# stepper.net
KiCad netlist of a schematic drawn in EAGLE
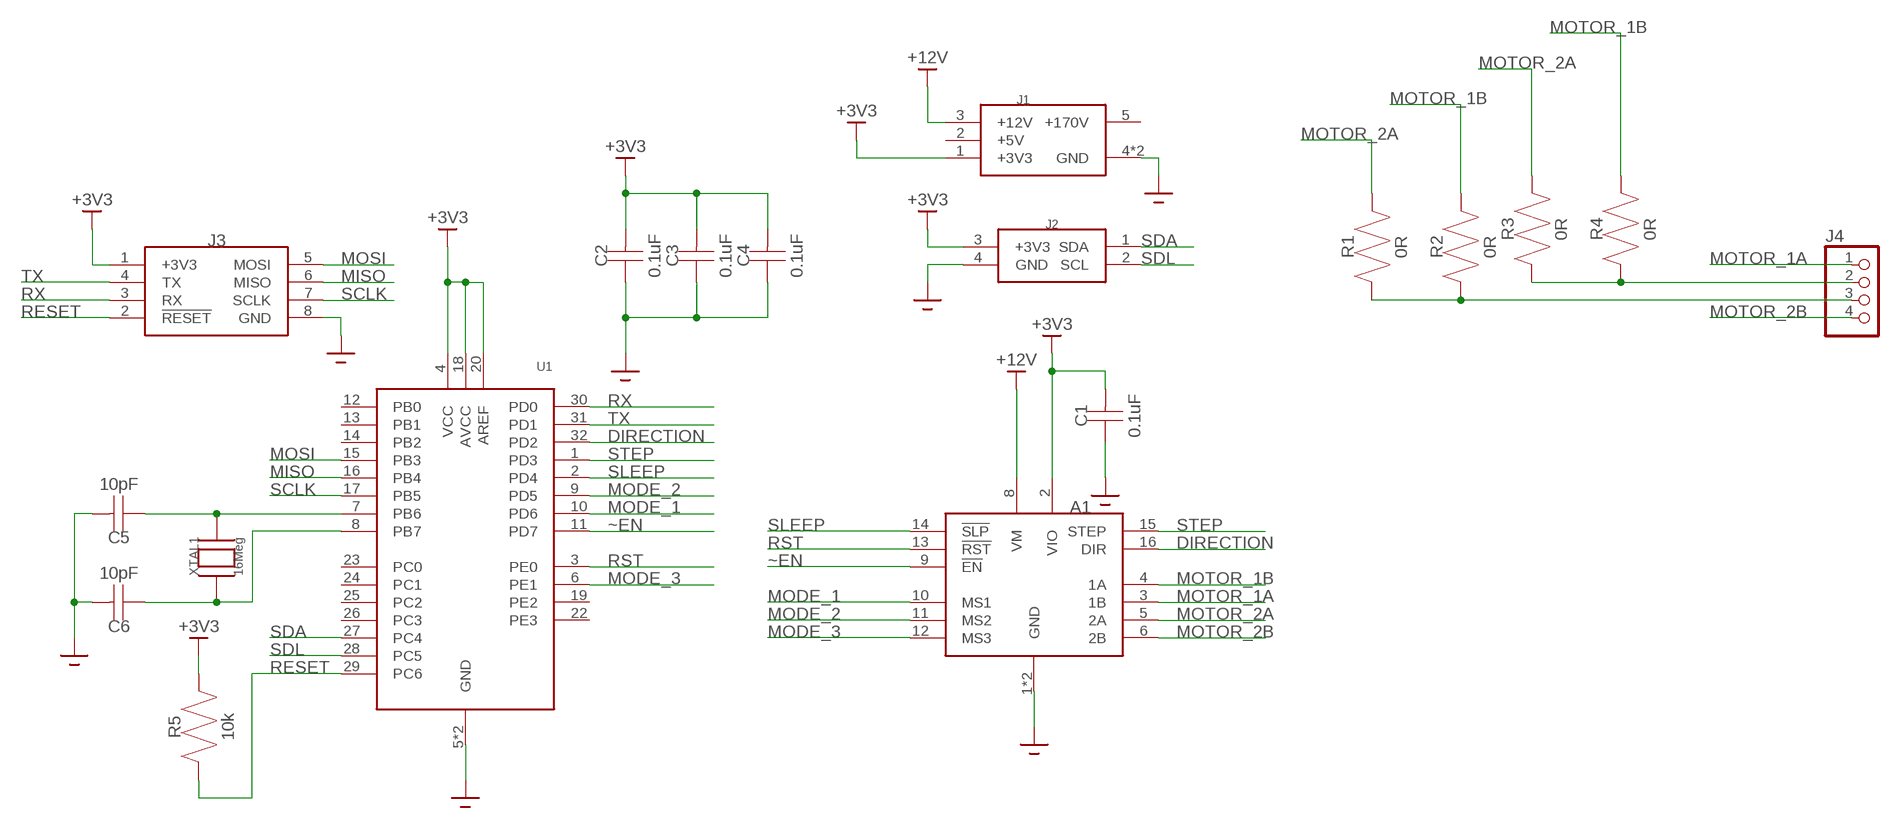
[diagram p0: schematic, sheet 1]

(export (version "E")
  (design (tool "Eeschema 10.0.6"))
  (components
    (comp (ref "A1")
      (value "STEPPER_DRIVER")
      (footprint "eagle-import:STEPPER_DRIVER")
      (libsource (lib "eagle-import") (part "STEPPER_DRIVER"))
    )
    (comp (ref "C1")
      (value "0.1uF")
      (footprint "eagle-import:0402")
      (libsource (lib "eagle-import") (part "CAPACITOR0402"))
    )
    (comp (ref "C2")
      (value "0.1uF")
      (footprint "eagle-import:0402")
      (libsource (lib "eagle-import") (part "CAPACITOR0402"))
    )
    (comp (ref "C3")
      (value "0.1uF")
      (footprint "eagle-import:0402")
      (libsource (lib "eagle-import") (part "CAPACITOR0402"))
    )
    (comp (ref "C4")
      (value "0.1uF")
      (footprint "eagle-import:0402")
      (libsource (lib "eagle-import") (part "CAPACITOR0402"))
    )
    (comp (ref "C5")
      (value "10pF")
      (footprint "eagle-import:0402")
      (libsource (lib "eagle-import") (part "CAPACITOR0402"))
    )
    (comp (ref "C6")
      (value "10pF")
      (footprint "eagle-import:0402")
      (libsource (lib "eagle-import") (part "CAPACITOR0402"))
    )
    (comp (ref "J1")
      (value "1-770969-0")
      (footprint "eagle-import:1-770969-0")
      (libsource (lib "eagle-import") (part "1-770969-0"))
    )
    (comp (ref "J2")
      (value "1-770968-0")
      (footprint "eagle-import:1-770968-0")
      (libsource (lib "eagle-import") (part "1-770968-0"))
    )
    (comp (ref "J3")
      (value "DF1BZ-8DP-2.5DSA")
      (footprint "eagle-import:DF1BZ-8DP-2.5DSA")
      (libsource (lib "eagle-import") (part "DF1BZ-8DP-2.5DSA"))
    )
    (comp (ref "J4")
      (value "S4B-XH-A")
      (footprint "eagle-import:S4B-XH-A")
      (libsource (lib "eagle-import") (part "S4B-XH-A"))
    )
    (comp (ref "R1")
      (value "0R")
      (footprint "eagle-import:0402")
      (libsource (lib "eagle-import") (part "RESISTOR0402"))
    )
    (comp (ref "R2")
      (value "0R")
      (footprint "eagle-import:0402")
      (libsource (lib "eagle-import") (part "RESISTOR0402"))
    )
    (comp (ref "R3")
      (value "0R")
      (footprint "eagle-import:0402")
      (libsource (lib "eagle-import") (part "RESISTOR0402"))
    )
    (comp (ref "R4")
      (value "0R")
      (footprint "eagle-import:0402")
      (libsource (lib "eagle-import") (part "RESISTOR0402"))
    )
    (comp (ref "R5")
      (value "10k")
      (footprint "eagle-import:0402")
      (libsource (lib "eagle-import") (part "RESISTOR0402"))
    )
    (comp (ref "U1")
      (value "ATMEGA328PB32-TQFP")
      (footprint "eagle-import:ATMEGA328PB")
      (libsource (lib "eagle-import") (part "ATMEGA328PB32-TQFP"))
    )
    (comp (ref "XTAL1")
      (value "16Meg")
      (footprint "eagle-import:XRCGB")
      (libsource (lib "eagle-import") (part "XRCGB"))
    )
  )
  (nets
    (net (code "1") (name "+3V3") (class "Default")
      (node (ref "A1") (pin "2") (pinfunction "VIO_2") (pintype "power_in"))
      (node (ref "C1") (pin "2") (pinfunction "P$2_2") (pintype "passive"))
      (node (ref "C2") (pin "2") (pinfunction "P$2_2") (pintype "passive"))
      (node (ref "C3") (pin "2") (pinfunction "P$2_2") (pintype "passive"))
      (node (ref "C4") (pin "2") (pinfunction "P$2_2") (pintype "passive"))
      (node (ref "J1") (pin "1") (pinfunction "+3V3_1") (pintype "power_in"))
      (node (ref "J2") (pin "3") (pinfunction "+3V3_3") (pintype "power_in"))
      (node (ref "J3") (pin "1") (pinfunction "+3V3_1") (pintype "power_in"))
      (node (ref "R5") (pin "2") (pinfunction "P$2_2") (pintype "passive"))
      (node (ref "U1") (pin "18") (pinfunction "AVCC_18") (pintype "power_in"))
      (node (ref "U1") (pin "20") (pinfunction "AREF_20") (pintype "power_in"))
      (node (ref "U1") (pin "4") (pinfunction "VCC_4") (pintype "power_in"))
    )
    (net (code "2") (name "+12V") (class "Default")
      (node (ref "A1") (pin "8") (pinfunction "VM_8") (pintype "power_in"))
      (node (ref "J1") (pin "3") (pinfunction "+12V_3") (pintype "power_in"))
    )
    (net (code "3") (name "/+5V") (class "Default")
      (node (ref "J1") (pin "2") (pinfunction "+5V_2") (pintype "power_in"))
    )
    (net (code "4") (name "/+170V") (class "Default")
      (node (ref "J1") (pin "5") (pinfunction "+170V_5") (pintype "power_in"))
    )
    (net (code "5") (name "/DIRECTION") (class "Default")
      (node (ref "A1") (pin "16") (pinfunction "DIR_16") (pintype "input"))
      (node (ref "U1") (pin "32") (pinfunction "PD2_32") (pintype "bidirectional"))
    )
    (net (code "6") (name "/MISO") (class "Default")
      (node (ref "J3") (pin "6") (pinfunction "MISO_6") (pintype "input"))
      (node (ref "U1") (pin "16") (pinfunction "PB4_16") (pintype "bidirectional"))
    )
    (net (code "7") (name "/MODE_1") (class "Default")
      (node (ref "A1") (pin "10") (pinfunction "MS1_10") (pintype "input"))
      (node (ref "U1") (pin "10") (pinfunction "PD6_10") (pintype "bidirectional"))
    )
    (net (code "8") (name "/MODE_2") (class "Default")
      (node (ref "A1") (pin "11") (pinfunction "MS2_11") (pintype "input"))
      (node (ref "U1") (pin "9") (pinfunction "PD5_9") (pintype "bidirectional"))
    )
    (net (code "9") (name "/MODE_3") (class "Default")
      (node (ref "A1") (pin "12") (pinfunction "MS3_12") (pintype "input"))
      (node (ref "U1") (pin "6") (pinfunction "PE1_6") (pintype "bidirectional"))
    )
    (net (code "10") (name "/MOSI") (class "Default")
      (node (ref "J3") (pin "5") (pinfunction "MOSI_5") (pintype "output"))
      (node (ref "U1") (pin "15") (pinfunction "PB3_15") (pintype "bidirectional"))
    )
    (net (code "11") (name "/MOTOR_1A") (class "Default")
      (node (ref "A1") (pin "3") (pinfunction "1B_3") (pintype "output"))
      (node (ref "J4") (pin "1") (pinfunction "1_1") (pintype "passive"))
    )
    (net (code "12") (name "/MOTOR_1B") (class "Default")
      (node (ref "A1") (pin "4") (pinfunction "1A_4") (pintype "output"))
      (node (ref "R2") (pin "2") (pinfunction "P$2_2") (pintype "passive"))
      (node (ref "R4") (pin "2") (pinfunction "P$2_2") (pintype "passive"))
    )
    (net (code "13") (name "/MOTOR_2A") (class "Default")
      (node (ref "A1") (pin "5") (pinfunction "2A_5") (pintype "output"))
      (node (ref "R1") (pin "2") (pinfunction "P$2_2") (pintype "passive"))
      (node (ref "R3") (pin "2") (pinfunction "P$2_2") (pintype "passive"))
    )
    (net (code "14") (name "/MOTOR_2B") (class "Default")
      (node (ref "A1") (pin "6") (pinfunction "2B_6") (pintype "output"))
      (node (ref "J4") (pin "4") (pinfunction "4_4") (pintype "passive"))
    )
    (net (code "15") (name "/RESET") (class "Default")
      (node (ref "J3") (pin "2") (pinfunction "~{RESET}_2") (pintype "output"))
      (node (ref "R5") (pin "1") (pinfunction "P$1_1") (pintype "passive"))
      (node (ref "U1") (pin "29") (pinfunction "PC6_29") (pintype "bidirectional"))
    )
    (net (code "16") (name "/RST") (class "Default")
      (node (ref "A1") (pin "13") (pinfunction "~{RST}_13") (pintype "input"))
      (node (ref "U1") (pin "3") (pinfunction "PE0_3") (pintype "bidirectional"))
    )
    (net (code "17") (name "/RX") (class "Default")
      (node (ref "J3") (pin "3") (pinfunction "RX_3") (pintype "output"))
      (node (ref "U1") (pin "30") (pinfunction "PD0_30") (pintype "bidirectional"))
    )
    (net (code "18") (name "/SCLK") (class "Default")
      (node (ref "J3") (pin "7") (pinfunction "SCLK_7") (pintype "output"))
      (node (ref "U1") (pin "17") (pinfunction "PB5_17") (pintype "bidirectional"))
    )
    (net (code "19") (name "/SDA") (class "Default")
      (node (ref "J2") (pin "1") (pinfunction "SDA_1") (pintype "bidirectional"))
      (node (ref "U1") (pin "27") (pinfunction "PC4_27") (pintype "bidirectional"))
    )
    (net (code "20") (name "/SDL") (class "Default")
      (node (ref "J2") (pin "2") (pinfunction "SCL_2") (pintype "bidirectional"))
      (node (ref "U1") (pin "28") (pinfunction "PC5_28") (pintype "bidirectional"))
    )
    (net (code "21") (name "/SLEEP") (class "Default")
      (node (ref "A1") (pin "14") (pinfunction "~{SLP}_14") (pintype "input"))
      (node (ref "U1") (pin "2") (pinfunction "PD4_2") (pintype "bidirectional"))
    )
    (net (code "22") (name "/STEP") (class "Default")
      (node (ref "A1") (pin "15") (pinfunction "STEP_15") (pintype "input"))
      (node (ref "U1") (pin "1") (pinfunction "PD3_1") (pintype "bidirectional"))
    )
    (net (code "23") (name "/TX") (class "Default")
      (node (ref "J3") (pin "4") (pinfunction "TX_4") (pintype "input"))
      (node (ref "U1") (pin "31") (pinfunction "PD1_31") (pintype "bidirectional"))
    )
    (net (code "24") (name "/~{EN}") (class "Default")
      (node (ref "A1") (pin "9") (pinfunction "~{EN}_9") (pintype "input"))
      (node (ref "U1") (pin "11") (pinfunction "PD7_11") (pintype "bidirectional"))
    )
    (net (code "25") (name "GND") (class "Default")
      (node (ref "A1") (pin "1") (pinfunction "GND_1") (pintype "passive"))
      (node (ref "A1") (pin "7") (pinfunction "GND_7") (pintype "passive"))
      (node (ref "C1") (pin "1") (pinfunction "P$1_1") (pintype "passive"))
      (node (ref "C2") (pin "1") (pinfunction "P$1_1") (pintype "passive"))
      (node (ref "C3") (pin "1") (pinfunction "P$1_1") (pintype "passive"))
      (node (ref "C4") (pin "1") (pinfunction "P$1_1") (pintype "passive"))
      (node (ref "C5") (pin "2") (pinfunction "P$2_2") (pintype "passive"))
      (node (ref "C6") (pin "2") (pinfunction "P$2_2") (pintype "passive"))
      (node (ref "J1") (pin "4") (pinfunction "GND_4") (pintype "passive"))
      (node (ref "J1") (pin "6") (pinfunction "GND_6") (pintype "passive"))
      (node (ref "J2") (pin "4") (pinfunction "GND_4") (pintype "passive"))
      (node (ref "J3") (pin "8") (pinfunction "GND_8") (pintype "passive"))
      (node (ref "U1") (pin "21") (pinfunction "GND_21") (pintype "passive"))
      (node (ref "U1") (pin "5") (pinfunction "GND_5") (pintype "passive"))
    )
    (net (code "26") (name "Net-(C5-P$1)") (class "Default")
      (node (ref "C5") (pin "1") (pinfunction "P$1_1") (pintype "passive"))
      (node (ref "U1") (pin "7") (pinfunction "PB6_7") (pintype "bidirectional"))
      (node (ref "XTAL1") (pin "2") (pinfunction "P$2_2") (pintype "passive"))
      (node (ref "XTAL1") (pin "4") (pinfunction "P$2_4") (pintype "passive"))
    )
    (net (code "27") (name "Net-(C6-P$1)") (class "Default")
      (node (ref "C6") (pin "1") (pinfunction "P$1_1") (pintype "passive"))
      (node (ref "U1") (pin "8") (pinfunction "PB7_8") (pintype "bidirectional"))
      (node (ref "XTAL1") (pin "1") (pinfunction "P$1_1") (pintype "passive"))
      (node (ref "XTAL1") (pin "3") (pinfunction "P$1_3") (pintype "passive"))
    )
    (net (code "28") (name "Net-(R1-P$1)") (class "Default")
      (node (ref "J4") (pin "3") (pinfunction "3_3") (pintype "passive"))
      (node (ref "R1") (pin "1") (pinfunction "P$1_1") (pintype "passive"))
      (node (ref "R2") (pin "1") (pinfunction "P$1_1") (pintype "passive"))
    )
    (net (code "29") (name "Net-(R3-P$1)") (class "Default")
      (node (ref "J4") (pin "2") (pinfunction "2_2") (pintype "passive"))
      (node (ref "R3") (pin "1") (pinfunction "P$1_1") (pintype "passive"))
      (node (ref "R4") (pin "1") (pinfunction "P$1_1") (pintype "passive"))
    )
    (net (code "30") (name "unconnected-(U1-PB0-Pad12)") (class "Default")
      (node (ref "U1") (pin "12") (pinfunction "PB0_12") (pintype "bidirectional"))
    )
    (net (code "31") (name "unconnected-(U1-PB1-Pad13)") (class "Default")
      (node (ref "U1") (pin "13") (pinfunction "PB1_13") (pintype "bidirectional"))
    )
    (net (code "32") (name "unconnected-(U1-PB2-Pad14)") (class "Default")
      (node (ref "U1") (pin "14") (pinfunction "PB2_14") (pintype "bidirectional"))
    )
    (net (code "33") (name "unconnected-(U1-PC0-Pad23)") (class "Default")
      (node (ref "U1") (pin "23") (pinfunction "PC0_23") (pintype "bidirectional"))
    )
    (net (code "34") (name "unconnected-(U1-PC1-Pad24)") (class "Default")
      (node (ref "U1") (pin "24") (pinfunction "PC1_24") (pintype "bidirectional"))
    )
    (net (code "35") (name "unconnected-(U1-PC2-Pad25)") (class "Default")
      (node (ref "U1") (pin "25") (pinfunction "PC2_25") (pintype "bidirectional"))
    )
    (net (code "36") (name "unconnected-(U1-PC3-Pad26)") (class "Default")
      (node (ref "U1") (pin "26") (pinfunction "PC3_26") (pintype "bidirectional"))
    )
    (net (code "37") (name "unconnected-(U1-PE2-Pad19)") (class "Default")
      (node (ref "U1") (pin "19") (pinfunction "PE2_19") (pintype "bidirectional"))
    )
    (net (code "38") (name "unconnected-(U1-PE3-Pad22)") (class "Default")
      (node (ref "U1") (pin "22") (pinfunction "PE3_22") (pintype "bidirectional"))
    )
  )
)
